# SwimWatch2_1.net
KiCad netlist of a schematic drawn in EAGLE
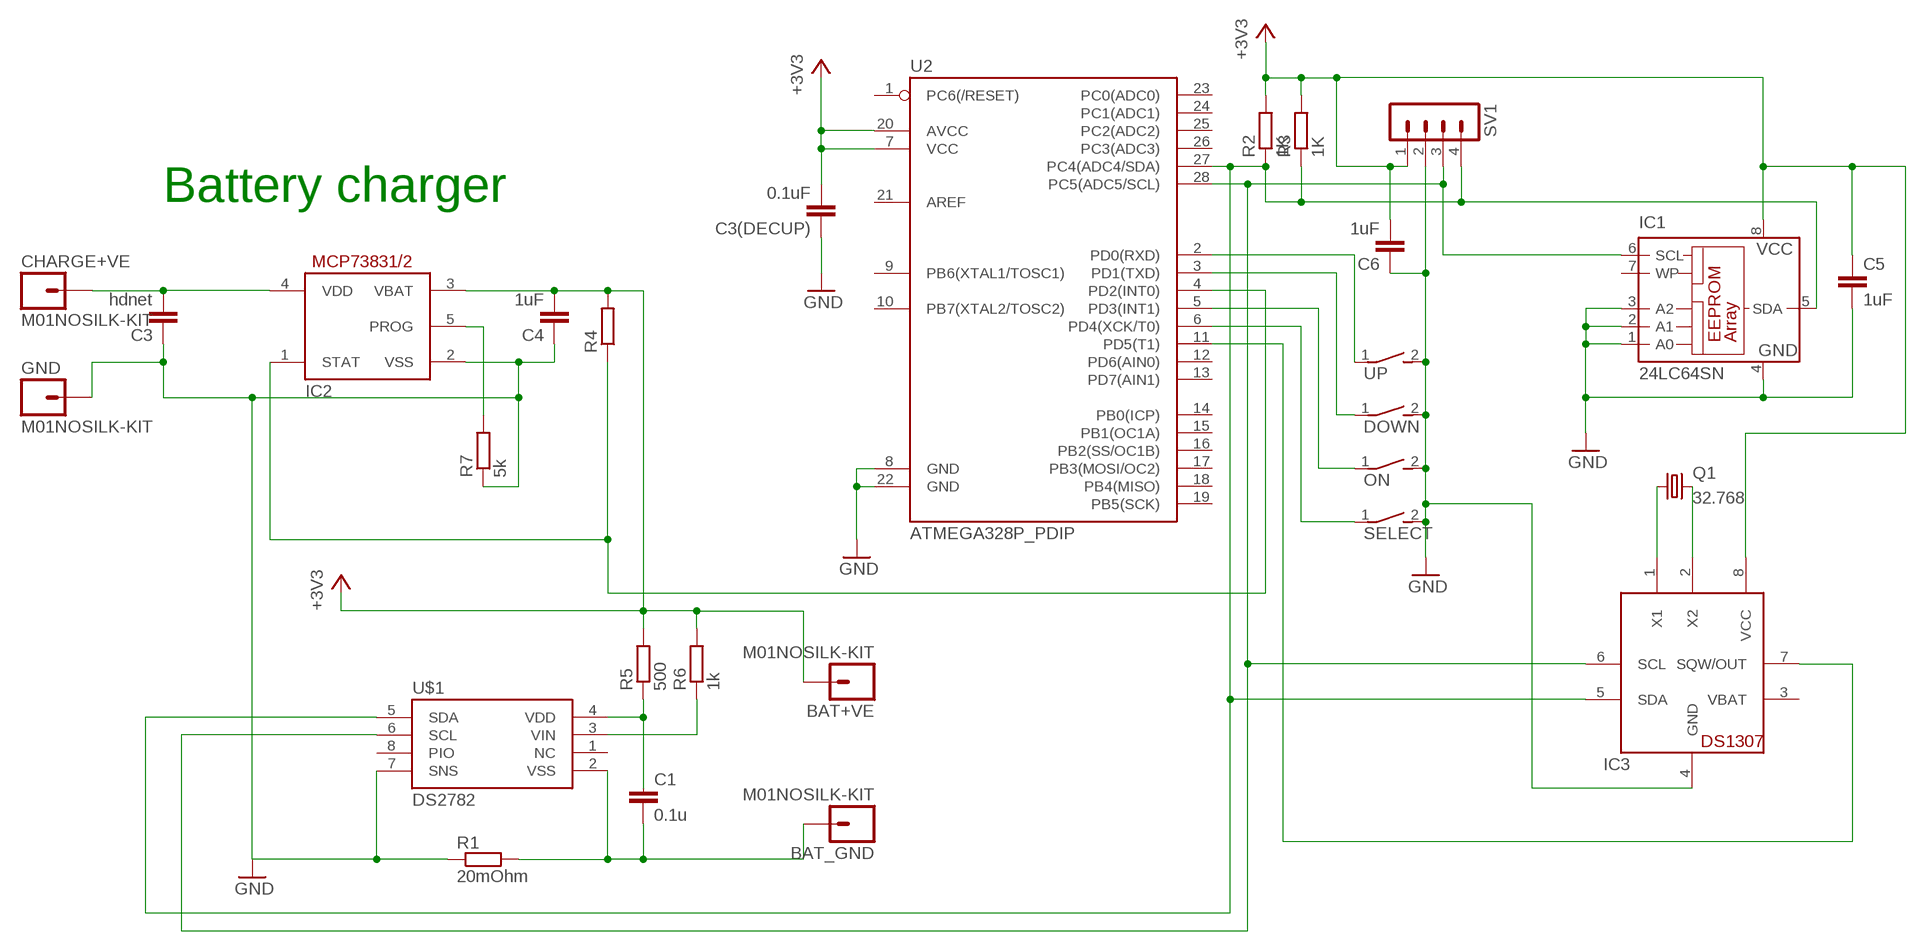
[diagram p0: schematic, sheet 1]

(export (version "E")
  (design (tool "Eeschema 10.0.6"))
  (components
    (comp (ref "BAT+VE")
      (value "M01NOSILK-KIT")
      (footprint "eagle-import:1X01NS-KIT")
      (libsource (lib "eagle-import") (part "M01NOSILK-KIT"))
    )
    (comp (ref "BAT_GND")
      (value "M01NOSILK-KIT")
      (footprint "eagle-import:1X01NS-KIT")
      (libsource (lib "eagle-import") (part "M01NOSILK-KIT"))
    )
    (comp (ref "C1")
      (value "0.1u")
      (footprint "eagle-import:C025-030X050")
      (libsource (lib "eagle-import") (part "C-EU025-030X050"))
    )
    (comp (ref "C3")
      (value "hdnet")
      (footprint "eagle-import:C0805")
      (libsource (lib "eagle-import") (part "C-EUC0805"))
    )
    (comp (ref "C3(DECUP)")
      (value "0.1uF")
      (footprint "eagle-import:C0805")
      (libsource (lib "eagle-import") (part "C-EUC0805"))
    )
    (comp (ref "C4")
      (value "1uF")
      (footprint "eagle-import:C0805")
      (libsource (lib "eagle-import") (part "C-EUC0805"))
    )
    (comp (ref "C5")
      (value "1uF")
      (footprint "eagle-import:C0805")
      (libsource (lib "eagle-import") (part "C-EUC0805"))
    )
    (comp (ref "C6")
      (value "1uF")
      (footprint "eagle-import:C0805")
      (libsource (lib "eagle-import") (part "C-EUC0805"))
    )
    (comp (ref "CHARGE+VE")
      (value "M01NOSILK-KIT")
      (footprint "eagle-import:1X01NS-KIT")
      (libsource (lib "eagle-import") (part "M01NOSILK-KIT"))
    )
    (comp (ref "DOWN")
      (value "DS01E")
      (footprint "eagle-import:DS-01")
      (libsource (lib "eagle-import") (part "DS01E"))
    )
    (comp (ref "GND")
      (value "M01NOSILK-KIT")
      (footprint "eagle-import:1X01NS-KIT")
      (libsource (lib "eagle-import") (part "M01NOSILK-KIT"))
    )
    (comp (ref "IC1")
      (value "24LC64SN")
      (footprint "eagle-import:SO-08")
      (fields (field (name "MF") "MICROCHIP") (field (name "MPN") "24LC64-I/SN"))
      (libsource (lib "eagle-import") (part "24SNLC64"))
    )
    (comp (ref "IC2")
      (value "MCP73831/OT")
      (footprint "eagle-import:SOT23-5L")
      (libsource (lib "eagle-import") (part "MCP73831/OT"))
    )
    (comp (ref "IC3")
      (value "DS1307")
      (footprint "eagle-import:DIL08")
      (libsource (lib "eagle-import") (part "DS1307"))
    )
    (comp (ref "ON")
      (value "DS01E")
      (footprint "eagle-import:DS-01")
      (libsource (lib "eagle-import") (part "DS01E"))
    )
    (comp (ref "Q1")
      (value "32.768")
      (footprint "eagle-import:HC18U-V")
      (libsource (lib "eagle-import") (part "CRYSTALHC18U-V"))
    )
    (comp (ref "R1")
      (value "20mOhm")
      (footprint "eagle-import:0204_5")
      (libsource (lib "eagle-import") (part "R-EU_0204/5"))
    )
    (comp (ref "R2")
      (value "1K")
      (footprint "eagle-import:M0805")
      (libsource (lib "eagle-import") (part "R-EU_M0805"))
    )
    (comp (ref "R3")
      (value "1K")
      (footprint "eagle-import:M0805")
      (libsource (lib "eagle-import") (part "R-EU_M0805"))
    )
    (comp (ref "R4")
      (value "R-EU_0204/5")
      (footprint "eagle-import:0204_5")
      (libsource (lib "eagle-import") (part "R-EU_0204/5"))
    )
    (comp (ref "R5")
      (value "500")
      (footprint "eagle-import:0204_5")
      (libsource (lib "eagle-import") (part "R-EU_0204/5"))
    )
    (comp (ref "R6")
      (value "1k")
      (footprint "eagle-import:0204_5")
      (libsource (lib "eagle-import") (part "R-EU_0204/5"))
    )
    (comp (ref "R7")
      (value "5k")
      (footprint "eagle-import:0204_5")
      (libsource (lib "eagle-import") (part "R-EU_0204/5"))
    )
    (comp (ref "SELECT")
      (value "DS01E")
      (footprint "eagle-import:DS-01")
      (libsource (lib "eagle-import") (part "DS01E"))
    )
    (comp (ref "SV1")
      (value "MA04-1")
      (footprint "eagle-import:MA04-1")
      (libsource (lib "eagle-import") (part "MA04-1"))
    )
    (comp (ref "U$1")
      (value "DS2782")
      (footprint "eagle-import:DS2782")
      (libsource (lib "eagle-import") (part "DS2782"))
    )
    (comp (ref "U2")
      (value "ATMEGA328P_PDIP")
      (footprint "eagle-import:DIL28-3")
      (libsource (lib "eagle-import") (part "ATMEGA328P_PDIP"))
    )
    (comp (ref "UP")
      (value "DS01E")
      (footprint "eagle-import:DS-01")
      (libsource (lib "eagle-import") (part "DS01E"))
    )
  )
  (nets
    (net (code "1") (name "+3V3") (class "Default")
      (node (ref "BAT+VE") (pin "1") (pinfunction "1_1") (pintype "passive"))
      (node (ref "C3(DECUP)") (pin "2") (pinfunction "2_2") (pintype "passive"))
      (node (ref "C4") (pin "2") (pinfunction "2_2") (pintype "passive"))
      (node (ref "C5") (pin "1") (pinfunction "1_1") (pintype "passive"))
      (node (ref "C6") (pin "2") (pinfunction "2_2") (pintype "passive"))
      (node (ref "IC1") (pin "8") (pinfunction "VCC_8") (pintype "power_in"))
      (node (ref "IC2") (pin "3") (pinfunction "VBAT_3") (pintype "bidirectional"))
      (node (ref "IC3") (pin "8") (pinfunction "VCC_8") (pintype "power_in"))
      (node (ref "R2") (pin "2") (pinfunction "2_2") (pintype "passive"))
      (node (ref "R3") (pin "2") (pinfunction "2_2") (pintype "passive"))
      (node (ref "R4") (pin "2") (pinfunction "2_2") (pintype "passive"))
      (node (ref "R5") (pin "2") (pinfunction "2_2") (pintype "passive"))
      (node (ref "R6") (pin "2") (pinfunction "2_2") (pintype "passive"))
      (node (ref "SV1") (pin "1") (pinfunction "1_1") (pintype "passive"))
      (node (ref "U2") (pin "20") (pinfunction "AVCC_20") (pintype "bidirectional"))
      (node (ref "U2") (pin "7") (pinfunction "VCC_7") (pintype "bidirectional"))
    )
    (net (code "2") (name "/VBAT") (class "Default")
      (node (ref "IC3") (pin "3") (pinfunction "VBAT_3") (pintype "power_in"))
    )
    (net (code "3") (name "GND") (class "Default")
      (node (ref "C3") (pin "1") (pinfunction "1_1") (pintype "passive"))
      (node (ref "C3(DECUP)") (pin "1") (pinfunction "1_1") (pintype "passive"))
      (node (ref "C4") (pin "1") (pinfunction "1_1") (pintype "passive"))
      (node (ref "C5") (pin "2") (pinfunction "2_2") (pintype "passive"))
      (node (ref "C6") (pin "1") (pinfunction "1_1") (pintype "passive"))
      (node (ref "DOWN") (pin "2") (pinfunction "2_2") (pintype "passive"))
      (node (ref "GND") (pin "1") (pinfunction "1_1") (pintype "passive"))
      (node (ref "IC1") (pin "1") (pinfunction "A0_1") (pintype "input"))
      (node (ref "IC1") (pin "2") (pinfunction "A1_2") (pintype "input"))
      (node (ref "IC1") (pin "3") (pinfunction "A2_3") (pintype "input"))
      (node (ref "IC1") (pin "4") (pinfunction "GND_4") (pintype "power_in"))
      (node (ref "IC2") (pin "2") (pinfunction "VSS_2") (pintype "power_in"))
      (node (ref "IC3") (pin "4") (pinfunction "GND_4") (pintype "power_in"))
      (node (ref "ON") (pin "2") (pinfunction "2_2") (pintype "passive"))
      (node (ref "R1") (pin "1") (pinfunction "1_1") (pintype "passive"))
      (node (ref "R7") (pin "1") (pinfunction "1_1") (pintype "passive"))
      (node (ref "SELECT") (pin "2") (pinfunction "2_2") (pintype "passive"))
      (node (ref "SV1") (pin "2") (pinfunction "2_2") (pintype "passive"))
      (node (ref "U$1") (pin "7") (pinfunction "SNS_7") (pintype "bidirectional"))
      (node (ref "U2") (pin "22") (pinfunction "GND_22") (pintype "bidirectional"))
      (node (ref "U2") (pin "8") (pinfunction "GND_8") (pintype "bidirectional"))
      (node (ref "UP") (pin "2") (pinfunction "2_2") (pintype "passive"))
    )
    (net (code "4") (name "Net-(IC1-SCL)") (class "Default")
      (node (ref "IC1") (pin "6") (pinfunction "SCL_6") (pintype "input"))
      (node (ref "IC3") (pin "6") (pinfunction "SCL_6") (pintype "bidirectional"))
      (node (ref "SV1") (pin "3") (pinfunction "3_3") (pintype "passive"))
      (node (ref "U$1") (pin "6") (pinfunction "SCL_6") (pintype "bidirectional"))
      (node (ref "U2") (pin "28") (pinfunction "PC5(ADC5/SCL)_28") (pintype "bidirectional"))
    )
    (net (code "5") (name "Net-(IC1-SDA)") (class "Default")
      (node (ref "IC1") (pin "5") (pinfunction "SDA_5") (pintype "bidirectional"))
      (node (ref "IC3") (pin "5") (pinfunction "SDA_5") (pintype "bidirectional"))
      (node (ref "R2") (pin "1") (pinfunction "1_1") (pintype "passive"))
      (node (ref "R3") (pin "1") (pinfunction "1_1") (pintype "passive"))
      (node (ref "SV1") (pin "4") (pinfunction "4_4") (pintype "passive"))
      (node (ref "U$1") (pin "5") (pinfunction "SDA_5") (pintype "bidirectional"))
      (node (ref "U2") (pin "27") (pinfunction "PC4(ADC4/SDA)_27") (pintype "bidirectional"))
    )
    (net (code "6") (name "Net-(IC2-PROG)") (class "Default")
      (node (ref "IC2") (pin "5") (pinfunction "PROG_5") (pintype "input"))
      (node (ref "R7") (pin "2") (pinfunction "2_2") (pintype "passive"))
    )
    (net (code "7") (name "Net-(IC2-STAT)") (class "Default")
      (node (ref "IC2") (pin "1") (pinfunction "STAT_1") (pintype "output"))
      (node (ref "R4") (pin "1") (pinfunction "1_1") (pintype "passive"))
      (node (ref "U2") (pin "4") (pinfunction "PD2(INT0)_4") (pintype "bidirectional"))
    )
    (net (code "8") (name "Net-(IC2-VDD)") (class "Default")
      (node (ref "C3") (pin "2") (pinfunction "2_2") (pintype "passive"))
      (node (ref "CHARGE+VE") (pin "1") (pinfunction "1_1") (pintype "passive"))
      (node (ref "IC2") (pin "4") (pinfunction "VDD_4") (pintype "power_in"))
    )
    (net (code "9") (name "Net-(IC3-SQW{slash}OUT)") (class "Default")
      (node (ref "IC3") (pin "7") (pinfunction "SQW/OUT_7") (pintype "bidirectional"))
      (node (ref "U2") (pin "11") (pinfunction "PD5(T1)_11") (pintype "bidirectional"))
    )
    (net (code "10") (name "Net-(IC3-X1)") (class "Default")
      (node (ref "IC3") (pin "1") (pinfunction "X1_1") (pintype "passive"))
      (node (ref "Q1") (pin "1") (pinfunction "1_1") (pintype "passive"))
    )
    (net (code "11") (name "Net-(IC3-X2)") (class "Default")
      (node (ref "IC3") (pin "2") (pinfunction "X2_2") (pintype "passive"))
      (node (ref "Q1") (pin "2") (pinfunction "2_2") (pintype "passive"))
    )
    (net (code "12") (name "Net-(U$1-VDD)") (class "Default")
      (node (ref "R5") (pin "1") (pinfunction "1_1") (pintype "passive"))
      (node (ref "U$1") (pin "4") (pinfunction "VDD_4") (pintype "bidirectional"))
    )
    (net (code "13") (name "Net-(U$1-VIN)") (class "Default")
      (node (ref "R6") (pin "1") (pinfunction "1_1") (pintype "passive"))
      (node (ref "U$1") (pin "3") (pinfunction "VIN_3") (pintype "bidirectional"))
    )
    (net (code "14") (name "Net-(U$1-VSS)") (class "Default")
      (node (ref "BAT_GND") (pin "1") (pinfunction "1_1") (pintype "passive"))
      (node (ref "C1") (pin "2") (pinfunction "2_2") (pintype "passive"))
      (node (ref "R1") (pin "2") (pinfunction "2_2") (pintype "passive"))
      (node (ref "U$1") (pin "2") (pinfunction "VSS_2") (pintype "bidirectional"))
    )
    (net (code "15") (name "Net-(U2-PD0(RXD))") (class "Default")
      (node (ref "U2") (pin "2") (pinfunction "PD0(RXD)_2") (pintype "bidirectional"))
      (node (ref "UP") (pin "1") (pinfunction "1_1") (pintype "passive"))
    )
    (net (code "16") (name "Net-(U2-PD1(TXD))") (class "Default")
      (node (ref "DOWN") (pin "1") (pinfunction "1_1") (pintype "passive"))
      (node (ref "U2") (pin "3") (pinfunction "PD1(TXD)_3") (pintype "bidirectional"))
    )
    (net (code "17") (name "Net-(U2-PD3(INT1))") (class "Default")
      (node (ref "ON") (pin "1") (pinfunction "1_1") (pintype "passive"))
      (node (ref "U2") (pin "5") (pinfunction "PD3(INT1)_5") (pintype "bidirectional"))
    )
    (net (code "18") (name "Net-(U2-PD4(XCK{slash}T0))") (class "Default")
      (node (ref "SELECT") (pin "1") (pinfunction "1_1") (pintype "passive"))
      (node (ref "U2") (pin "6") (pinfunction "PD4(XCK/T0)_6") (pintype "bidirectional"))
    )
    (net (code "19") (name "unconnected-(C1-Pad1)") (class "Default")
      (node (ref "C1") (pin "1") (pinfunction "1_1") (pintype "passive"))
    )
    (net (code "20") (name "unconnected-(IC1-WP-Pad7)") (class "Default")
      (node (ref "IC1") (pin "7") (pinfunction "WP_7") (pintype "input"))
    )
    (net (code "21") (name "unconnected-(U$1-NC-Pad1)") (class "Default")
      (node (ref "U$1") (pin "1") (pinfunction "NC_1") (pintype "bidirectional"))
    )
    (net (code "22") (name "unconnected-(U$1-PIO-Pad8)") (class "Default")
      (node (ref "U$1") (pin "8") (pinfunction "PIO_8") (pintype "bidirectional"))
    )
    (net (code "23") (name "unconnected-(U2-AREF-Pad21)") (class "Default")
      (node (ref "U2") (pin "21") (pinfunction "AREF_21") (pintype "bidirectional"))
    )
    (net (code "24") (name "unconnected-(U2-PB0(ICP)-Pad14)") (class "Default")
      (node (ref "U2") (pin "14") (pinfunction "PB0(ICP)_14") (pintype "bidirectional"))
    )
    (net (code "25") (name "unconnected-(U2-PB1(OC1A)-Pad15)") (class "Default")
      (node (ref "U2") (pin "15") (pinfunction "PB1(OC1A)_15") (pintype "bidirectional"))
    )
    (net (code "26") (name "unconnected-(U2-PB2(SS{slash}OC1B)-Pad16)") (class "Default")
      (node (ref "U2") (pin "16") (pinfunction "PB2(SS/OC1B)_16") (pintype "bidirectional"))
    )
    (net (code "27") (name "unconnected-(U2-PB3(MOSI{slash}OC2)-Pad17)") (class "Default")
      (node (ref "U2") (pin "17") (pinfunction "PB3(MOSI/OC2)_17") (pintype "bidirectional"))
    )
    (net (code "28") (name "unconnected-(U2-PB4(MISO)-Pad18)") (class "Default")
      (node (ref "U2") (pin "18") (pinfunction "PB4(MISO)_18") (pintype "bidirectional"))
    )
    (net (code "29") (name "unconnected-(U2-PB5(SCK)-Pad19)") (class "Default")
      (node (ref "U2") (pin "19") (pinfunction "PB5(SCK)_19") (pintype "bidirectional"))
    )
    (net (code "30") (name "unconnected-(U2-PB6(XTAL1{slash}TOSC1)-Pad9)") (class "Default")
      (node (ref "U2") (pin "9") (pinfunction "PB6(XTAL1/TOSC1)_9") (pintype "bidirectional"))
    )
    (net (code "31") (name "unconnected-(U2-PB7(XTAL2{slash}TOSC2)-Pad10)") (class "Default")
      (node (ref "U2") (pin "10") (pinfunction "PB7(XTAL2/TOSC2)_10") (pintype "bidirectional"))
    )
    (net (code "32") (name "unconnected-(U2-PC0(ADC0)-Pad23)") (class "Default")
      (node (ref "U2") (pin "23") (pinfunction "PC0(ADC0)_23") (pintype "bidirectional"))
    )
    (net (code "33") (name "unconnected-(U2-PC1(ADC1)-Pad24)") (class "Default")
      (node (ref "U2") (pin "24") (pinfunction "PC1(ADC1)_24") (pintype "bidirectional"))
    )
    (net (code "34") (name "unconnected-(U2-PC2(ADC2)-Pad25)") (class "Default")
      (node (ref "U2") (pin "25") (pinfunction "PC2(ADC2)_25") (pintype "bidirectional"))
    )
    (net (code "35") (name "unconnected-(U2-PC3(ADC3)-Pad26)") (class "Default")
      (node (ref "U2") (pin "26") (pinfunction "PC3(ADC3)_26") (pintype "bidirectional"))
    )
    (net (code "36") (name "unconnected-(U2-PC6({slash}RESET)-Pad1)") (class "Default")
      (node (ref "U2") (pin "1") (pinfunction "PC6(/RESET)_1") (pintype "bidirectional"))
    )
    (net (code "37") (name "unconnected-(U2-PD6(AIN0)-Pad12)") (class "Default")
      (node (ref "U2") (pin "12") (pinfunction "PD6(AIN0)_12") (pintype "bidirectional"))
    )
    (net (code "38") (name "unconnected-(U2-PD7(AIN1)-Pad13)") (class "Default")
      (node (ref "U2") (pin "13") (pinfunction "PD7(AIN1)_13") (pintype "bidirectional"))
    )
  )
)
